# VREF_ADR130A.net
KiCad netlist of a schematic drawn in Altium Designer
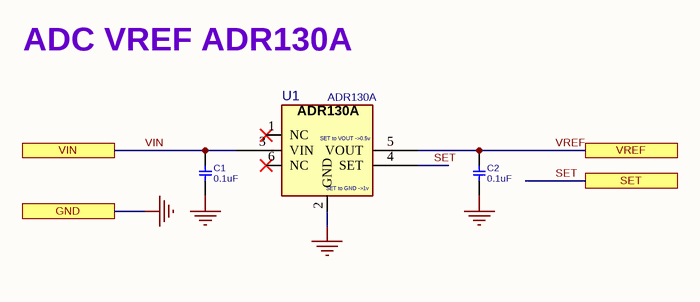
[diagram p0: VREF_ADR130A.SchDoc]

(export (version "E")
  (design (tool "Eeschema 10.0.6"))
  (components
    (comp (ref "C1")
      (value "0.1uF")
      (footprint "C0402")
      (description "CAP, MLCC")
      (libsource (lib "mlcc_smd_passive") (part "CAP_SMD_MLCC_100n50T"))
    )
    (comp (ref "C2")
      (value "0.1uF")
      (footprint "C0402")
      (description "CAP, MLCC")
      (libsource (lib "mlcc_smd_passive") (part "CAP_SMD_MLCC_100n50T"))
    )
    (comp (ref "U1")
      (value "ADR130A")
      (footprint "SOT23_6")
      (description "VREF, Sub-Band Gap")
      (fields (field (name "MANF") "Analog Devices") (field (name "MANF_P#") "ADR130AUJZ"))
      (libsource (lib "voltage_ref") (part "ADR130A_SOT23"))
    )
  )
  (nets
    (net (code "1") (name "/SET") (class "Default")
      (node (ref "U1") (pin "4") (pinfunction "SET_4") (pintype "passive"))
    )
    (net (code "2") (name "/VIN") (class "Default")
      (node (ref "C1") (pin "1") (pinfunction "1_1") (pintype "passive"))
      (node (ref "U1") (pin "3") (pinfunction "VIN_3") (pintype "passive"))
    )
    (net (code "3") (name "/VREF") (class "Default")
      (node (ref "C2") (pin "1") (pinfunction "1_1") (pintype "passive"))
      (node (ref "U1") (pin "5") (pinfunction "VOUT_5") (pintype "passive"))
    )
    (net (code "4") (name "GND") (class "Default")
      (node (ref "C1") (pin "2") (pinfunction "2_2") (pintype "passive"))
      (node (ref "C2") (pin "2") (pinfunction "2_2") (pintype "passive"))
      (node (ref "U1") (pin "2") (pinfunction "GND_2") (pintype "passive"))
    )
    (net (code "5") (name "unconnected-(U1-NC-Pad1)") (class "Default")
      (node (ref "U1") (pin "1") (pinfunction "NC_1") (pintype "passive+no_connect"))
    )
    (net (code "6") (name "unconnected-(U1-NC-Pad6)") (class "Default")
      (node (ref "U1") (pin "6") (pinfunction "NC_6") (pintype "passive+no_connect"))
    )
  )
)
